# LM331vs6N137.net
KiCad netlist of a schematic drawn in Altium Designer
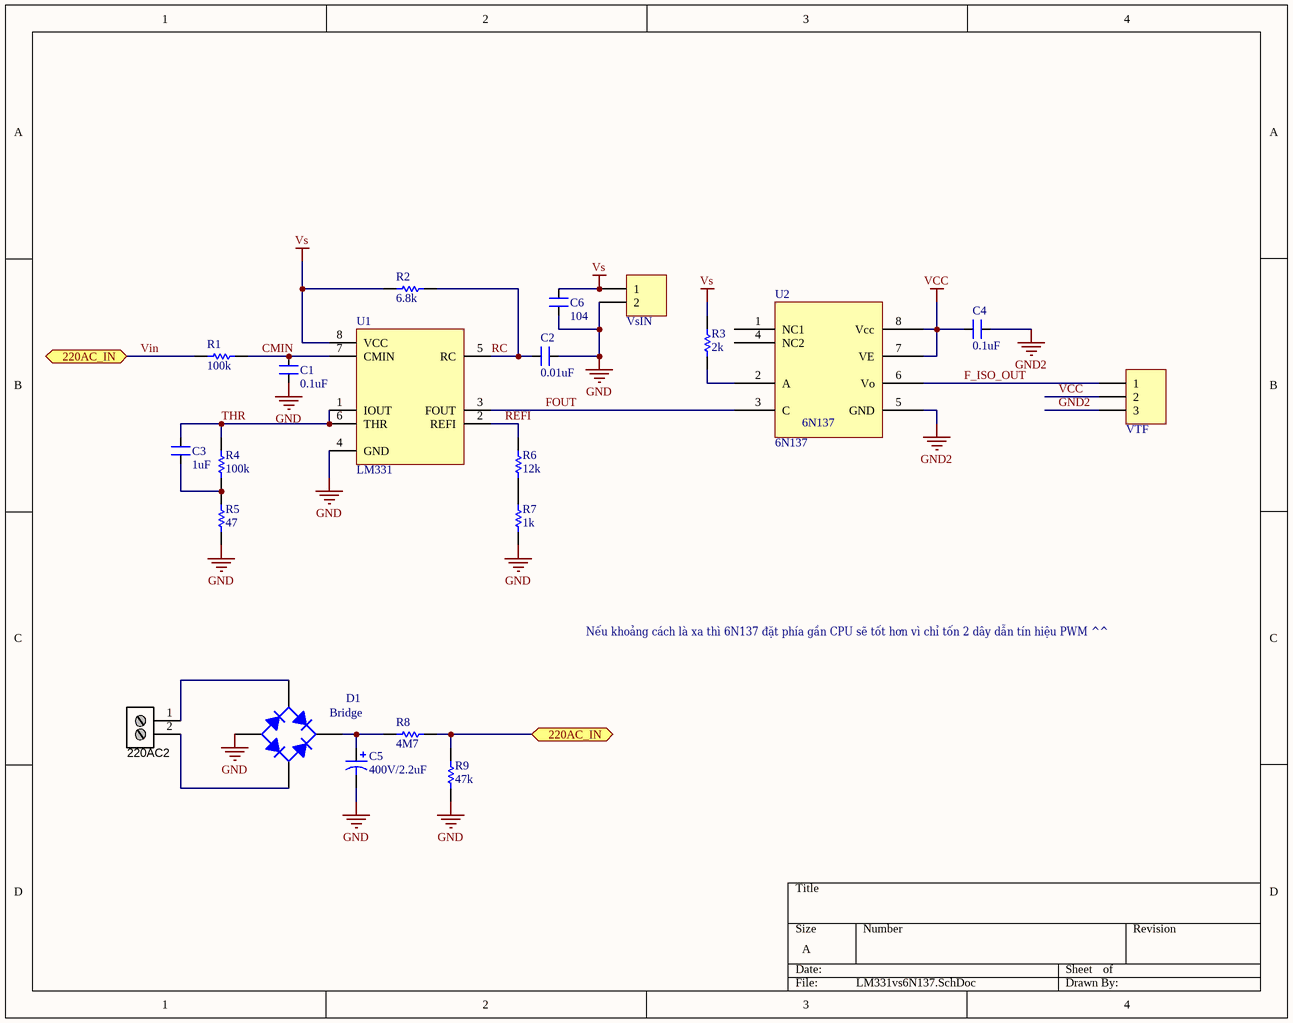
[diagram p0: LM331vs6N137.SchDoc]

(export (version "E")
  (design (tool "Eeschema 10.0.6"))
  (components
    (comp (ref "220AC2")
      (value "Stackable ScrewTerm")
      (footprint "2P_PCB_ScrewTerm_200mil")
      (description "Terminal Block Screw Type THT 2-Position 3.81mm pitch")
      (libsource (lib "PBL - Connectors") (part "2P_ScrewTerm_90S_3.81MM"))
    )
    (comp (ref "C1")
      (value "0.1uF")
      (footprint "CAPC2012N_F")
      (fields (field (name "Comment") "CAP NP"))
      (libsource (lib "Tuan") (part "CAP NP"))
    )
    (comp (ref "C2")
      (value "0.01uF")
      (footprint "CAPC2012N_F")
      (fields (field (name "Comment") "CAP NP"))
      (libsource (lib "Tuan") (part "CAP NP"))
    )
    (comp (ref "C3")
      (value "1uF")
      (footprint "CAPC2012N_F")
      (fields (field (name "Comment") "CAP NP"))
      (libsource (lib "Tuan") (part "CAP NP"))
    )
    (comp (ref "C4")
      (value "0.1uF")
      (footprint "CAPC2012N_F")
      (fields (field (name "Comment") "CAP NP"))
      (libsource (lib "Tuan") (part "CAP NP"))
    )
    (comp (ref "C5")
      (value "400V/2.2uF")
      (footprint "CAP 3.8mm")
      (fields (field (name "Comment") "Cap"))
      (libsource (lib "Tuan") (part "Cap"))
    )
    (comp (ref "C6")
      (value "104")
      (footprint "CAPC2012N_F")
      (fields (field (name "Comment") "CAP NP"))
      (libsource (lib "Tuan") (part "CAP NP"))
    )
    (comp (ref "D1")
      (value "Bridge")
      (footprint "MB6S")
      (description "Full Wave Diode Bridge")
      (fields (field (name "PUBLISHER") "Altium Limited"))
      (libsource (lib "Miscellaneous Devices") (part "Bridge1"))
    )
    (comp (ref "R1")
      (value "100k")
      (footprint "RESC2012N_F")
      (fields (field (name "Comment") "Res"))
      (libsource (lib "Tuan") (part "Res"))
    )
    (comp (ref "R2")
      (value "6.8k")
      (footprint "RESC2012N_F")
      (fields (field (name "Comment") "Res"))
      (libsource (lib "Tuan") (part "Res"))
    )
    (comp (ref "R3")
      (value "2k")
      (footprint "RESC2012N_F")
      (fields (field (name "Comment") "Res"))
      (libsource (lib "Tuan") (part "Res"))
    )
    (comp (ref "R4")
      (value "100k")
      (footprint "RESC2012N_F")
      (fields (field (name "Comment") "Res"))
      (libsource (lib "Tuan") (part "Res"))
    )
    (comp (ref "R5")
      (value "47")
      (footprint "RESC2012N_F")
      (fields (field (name "Comment") "Res"))
      (libsource (lib "Tuan") (part "Res"))
    )
    (comp (ref "R6")
      (value "12k")
      (footprint "RESC2012N_F")
      (fields (field (name "Comment") "Res"))
      (libsource (lib "Tuan") (part "Res"))
    )
    (comp (ref "R7")
      (value "1k")
      (footprint "RESC2012N_F")
      (fields (field (name "Comment") "Res"))
      (libsource (lib "Tuan") (part "Res"))
    )
    (comp (ref "R8")
      (value "4M7")
      (footprint "RESTH_0.0R_AXIAL-0.6")
      (fields (field (name "Comment") "Res"))
      (libsource (lib "Tuan") (part "Res"))
    )
    (comp (ref "R9")
      (value "47k")
      (footprint "RESTH_0.0R_AXIAL-0.6")
      (fields (field (name "Comment") "Res"))
      (libsource (lib "Tuan") (part "Res"))
    )
    (comp (ref "U1") (value "LM331") (footprint "DIP8-300") (libsource (lib "Tuan") (part "LM331")))
    (comp (ref "U2") (value "6N137") (footprint "SMD-8") (libsource (lib "Tuan") (part "6N137")))
    (comp (ref "VsIN")
      (value "Header 2")
      (footprint "heromap:HDR1X2")
      (description "Header, 2-Pin")
      (fields (field (name "PUBLISHER") "Altium Limited"))
      (libsource (lib "heromap") (part "Header 2"))
    )
    (comp (ref "VTF")
      (value "Header 3")
      (footprint "heromap:HDR1X3")
      (description "Header, 3-Pin")
      (fields (field (name "PUBLISHER") "Altium Limited"))
      (libsource (lib "heromap") (part "Header 3"))
    )
  )
  (nets
    (net (code "1") (name "/CMIN") (class "Default")
      (node (ref "C1") (pin "2") (pinfunction "2_2") (pintype "passive"))
      (node (ref "R1") (pin "2") (pinfunction "2_2") (pintype "passive"))
      (node (ref "U1") (pin "7") (pinfunction "CMIN_7") (pintype "passive"))
    )
    (net (code "2") (name "/FOUT") (class "Default")
      (node (ref "U1") (pin "3") (pinfunction "FOUT_3") (pintype "passive"))
      (node (ref "U2") (pin "3") (pinfunction "C_3") (pintype "passive"))
    )
    (net (code "3") (name "/F_ISO_OUT") (class "Default")
      (node (ref "U2") (pin "6") (pinfunction "Vo_6") (pintype "passive"))
      (node (ref "VTF") (pin "1") (pinfunction "1_1") (pintype "passive"))
    )
    (net (code "4") (name "/RC") (class "Default")
      (node (ref "C2") (pin "2") (pinfunction "2_2") (pintype "passive"))
      (node (ref "R2") (pin "2") (pinfunction "2_2") (pintype "passive"))
      (node (ref "U1") (pin "5") (pinfunction "RC_5") (pintype "passive"))
    )
    (net (code "5") (name "/REFI") (class "Default")
      (node (ref "R6") (pin "2") (pinfunction "2_2") (pintype "passive"))
      (node (ref "U1") (pin "2") (pinfunction "REFI_2") (pintype "passive"))
    )
    (net (code "6") (name "/THR") (class "Default")
      (node (ref "C3") (pin "1") (pinfunction "1_1") (pintype "passive"))
      (node (ref "R4") (pin "2") (pinfunction "2_2") (pintype "passive"))
      (node (ref "U1") (pin "1") (pinfunction "IOUT_1") (pintype "passive"))
      (node (ref "U1") (pin "6") (pinfunction "THR_6") (pintype "passive"))
    )
    (net (code "7") (name "/Vin") (class "Default")
      (node (ref "R1") (pin "1") (pinfunction "1_1") (pintype "passive"))
      (node (ref "R8") (pin "2") (pinfunction "2_2") (pintype "passive"))
      (node (ref "R9") (pin "2") (pinfunction "2_2") (pintype "passive"))
    )
    (net (code "8") (name "GND") (class "Default")
      (node (ref "C1") (pin "1") (pinfunction "1_1") (pintype "passive"))
      (node (ref "C2") (pin "1") (pinfunction "1_1") (pintype "passive"))
      (node (ref "C5") (pin "2") (pinfunction "2_2") (pintype "passive"))
      (node (ref "C6") (pin "1") (pinfunction "1_1") (pintype "passive"))
      (node (ref "D1") (pin "3") (pinfunction "A_3") (pintype "passive"))
      (node (ref "R5") (pin "1") (pinfunction "1_1") (pintype "passive"))
      (node (ref "R7") (pin "1") (pinfunction "1_1") (pintype "passive"))
      (node (ref "R9") (pin "1") (pinfunction "1_1") (pintype "passive"))
      (node (ref "U1") (pin "4") (pinfunction "GND_4") (pintype "passive"))
      (node (ref "VsIN") (pin "2") (pinfunction "2_2") (pintype "passive"))
    )
    (net (code "9") (name "GND2") (class "Default")
      (node (ref "C4") (pin "1") (pinfunction "1_1") (pintype "passive"))
      (node (ref "U2") (pin "5") (pinfunction "GND_5") (pintype "passive"))
      (node (ref "VTF") (pin "3") (pinfunction "3_3") (pintype "passive"))
    )
    (net (code "10") (name "Net-(220AC2-Pad1)") (class "Default")
      (node (ref "220AC2") (pin "1") (pinfunction "1_1") (pintype "passive"))
      (node (ref "D1") (pin "4") (pinfunction "C_4") (pintype "passive"))
    )
    (net (code "11") (name "Net-(220AC2-Pad2)") (class "Default")
      (node (ref "220AC2") (pin "2") (pinfunction "2_2") (pintype "passive"))
      (node (ref "D1") (pin "2") (pinfunction "C_2") (pintype "passive"))
    )
    (net (code "12") (name "Net-(C3-Pad2)") (class "Default")
      (node (ref "C3") (pin "2") (pinfunction "2_2") (pintype "passive"))
      (node (ref "R4") (pin "1") (pinfunction "1_1") (pintype "passive"))
      (node (ref "R5") (pin "2") (pinfunction "2_2") (pintype "passive"))
    )
    (net (code "13") (name "Net-(D1-K)") (class "Default")
      (node (ref "C5") (pin "1") (pinfunction "1_1") (pintype "passive"))
      (node (ref "D1") (pin "1") (pinfunction "K_1") (pintype "passive"))
      (node (ref "R8") (pin "1") (pinfunction "1_1") (pintype "passive"))
    )
    (net (code "14") (name "Net-(R6-Pad1)") (class "Default")
      (node (ref "R6") (pin "1") (pinfunction "1_1") (pintype "passive"))
      (node (ref "R7") (pin "2") (pinfunction "2_2") (pintype "passive"))
    )
    (net (code "15") (name "Net-(U2-A)") (class "Default")
      (node (ref "R3") (pin "1") (pinfunction "1_1") (pintype "passive"))
      (node (ref "U2") (pin "2") (pinfunction "A_2") (pintype "passive"))
    )
    (net (code "16") (name "VCC") (class "Default")
      (node (ref "C4") (pin "2") (pinfunction "2_2") (pintype "passive"))
      (node (ref "U2") (pin "7") (pinfunction "VE_7") (pintype "passive"))
      (node (ref "U2") (pin "8") (pinfunction "Vcc_8") (pintype "passive"))
      (node (ref "VTF") (pin "2") (pinfunction "2_2") (pintype "passive"))
    )
    (net (code "17") (name "Vs") (class "Default")
      (node (ref "C6") (pin "2") (pinfunction "2_2") (pintype "passive"))
      (node (ref "R2") (pin "1") (pinfunction "1_1") (pintype "passive"))
      (node (ref "R3") (pin "2") (pinfunction "2_2") (pintype "passive"))
      (node (ref "U1") (pin "8") (pinfunction "VCC_8") (pintype "passive"))
      (node (ref "VsIN") (pin "1") (pinfunction "1_1") (pintype "passive"))
    )
    (net (code "18") (name "unconnected-(U2-NC1-Pad1)") (class "Default")
      (node (ref "U2") (pin "1") (pinfunction "NC1_1") (pintype "passive"))
    )
    (net (code "19") (name "unconnected-(U2-NC2-Pad4)") (class "Default")
      (node (ref "U2") (pin "4") (pinfunction "NC2_4") (pintype "passive"))
    )
  )
)
